# IR_Sensor_Schematic.net
KiCad netlist of a schematic drawn in EAGLE
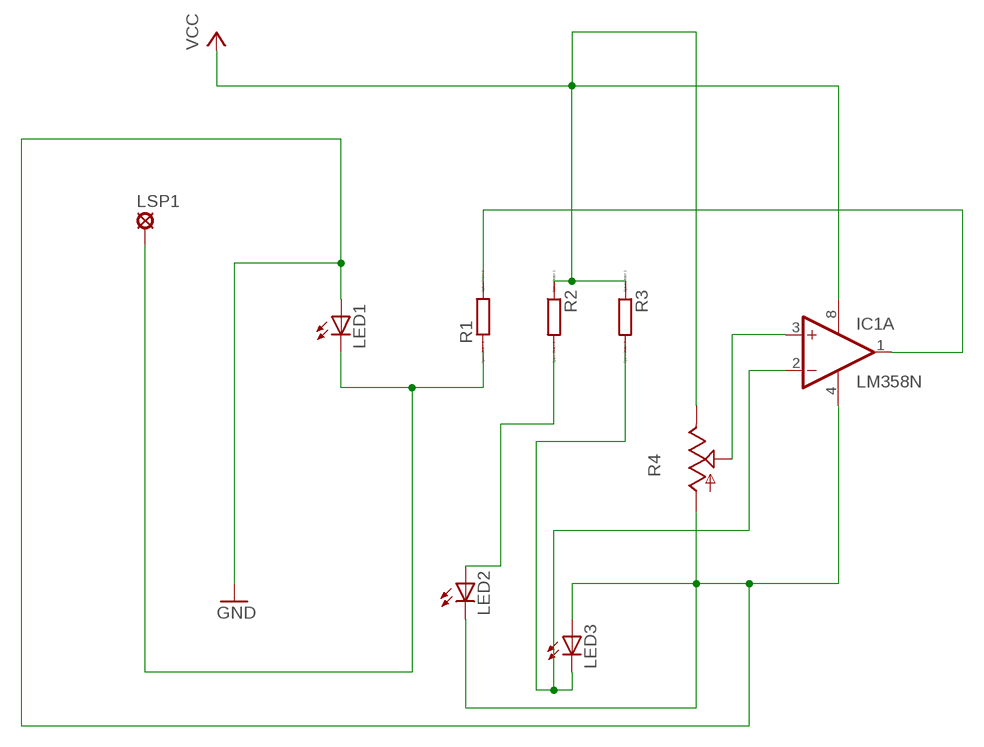
[diagram p0: schematic, sheet 1]

(export (version "E")
  (design (tool "Eeschema 10.0.6"))
  (components
    (comp (ref "IC1")
      (value "LM358N")
      (footprint "eagle-import:DIL08")
      (libsource (lib "eagle-import") (part "LM358N"))
    )
    (comp (ref "LED1")
      (value "LED5MM")
      (footprint "eagle-import:LED5MM")
      (libsource (lib "eagle-import") (part "LED5MM"))
    )
    (comp (ref "LED2")
      (value "LED5MM")
      (footprint "eagle-import:LED5MM")
      (libsource (lib "eagle-import") (part "LED5MM"))
    )
    (comp (ref "LED3")
      (value "LED5MM")
      (footprint "eagle-import:LED5MM")
      (libsource (lib "eagle-import") (part "LED5MM"))
    )
    (comp (ref "LSP1")
      (value "LSP10")
      (footprint "eagle-import:LSP10")
      (libsource (lib "eagle-import") (part "LSP10"))
    )
    (comp (ref "R1")
      (value "R-EU_0207_10")
      (footprint "eagle-import:0207_10")
      (libsource (lib "eagle-import") (part "R-EU_0207_10"))
    )
    (comp (ref "R2")
      (value "R-EU_0207_10")
      (footprint "eagle-import:0207_10")
      (libsource (lib "eagle-import") (part "R-EU_0207_10"))
    )
    (comp (ref "R3")
      (value "R-EU_0207_10")
      (footprint "eagle-import:0207_10")
      (libsource (lib "eagle-import") (part "R-EU_0207_10"))
    )
    (comp (ref "R4")
      (value "TRIM_US-LI15")
      (footprint "eagle-import:LI15")
      (libsource (lib "eagle-import") (part "TRIM_US-LI15"))
    )
  )
  (nets
    (net (code "1") (name "GND") (class "Default")
      (node (ref "IC1") (pin "4") (pinfunction "V-_4") (pintype "power_in"))
      (node (ref "LED1") (pin "A") (pinfunction "A_A") (pintype "passive"))
      (node (ref "LED2") (pin "K") (pinfunction "C_K") (pintype "passive"))
      (node (ref "LED3") (pin "A") (pinfunction "A_A") (pintype "passive"))
      (node (ref "R4") (pin "A") (pinfunction "A_A") (pintype "passive"))
    )
    (net (code "2") (name "Net-(IC1A-+IN)") (class "Default")
      (node (ref "IC1") (pin "3") (pinfunction "+IN_3") (pintype "input"))
      (node (ref "R4") (pin "S") (pinfunction "S_S") (pintype "passive"))
    )
    (net (code "3") (name "Net-(IC1A--IN)") (class "Default")
      (node (ref "IC1") (pin "2") (pinfunction "-IN_2") (pintype "input"))
      (node (ref "LED3") (pin "K") (pinfunction "C_K") (pintype "passive"))
      (node (ref "R3") (pin "2") (pinfunction "2_2") (pintype "passive"))
    )
    (net (code "4") (name "Net-(IC1A-OUT)") (class "Default")
      (node (ref "IC1") (pin "1") (pinfunction "OUT_1") (pintype "output"))
      (node (ref "R1") (pin "2") (pinfunction "2_2") (pintype "passive"))
    )
    (net (code "5") (name "Net-(LED1-C)") (class "Default")
      (node (ref "LED1") (pin "K") (pinfunction "C_K") (pintype "passive"))
      (node (ref "LSP1") (pin "MP") (pinfunction "MP_MP") (pintype "passive"))
      (node (ref "R1") (pin "1") (pinfunction "1_1") (pintype "passive"))
    )
    (net (code "6") (name "Net-(LED2-PadA)") (class "Default")
      (node (ref "LED2") (pin "A") (pinfunction "A_A") (pintype "passive"))
      (node (ref "R2") (pin "2") (pinfunction "2_2") (pintype "passive"))
    )
    (net (code "7") (name "VCC") (class "Default")
      (node (ref "IC1") (pin "8") (pinfunction "V+_8") (pintype "power_in"))
      (node (ref "R2") (pin "1") (pinfunction "1_1") (pintype "passive"))
      (node (ref "R3") (pin "1") (pinfunction "1_1") (pintype "passive"))
      (node (ref "R4") (pin "E") (pinfunction "E_E") (pintype "passive"))
    )
  )
)
